# 03_ATSAM3X_LFBGA217.net
KiCad netlist of a schematic drawn in Altium Designer
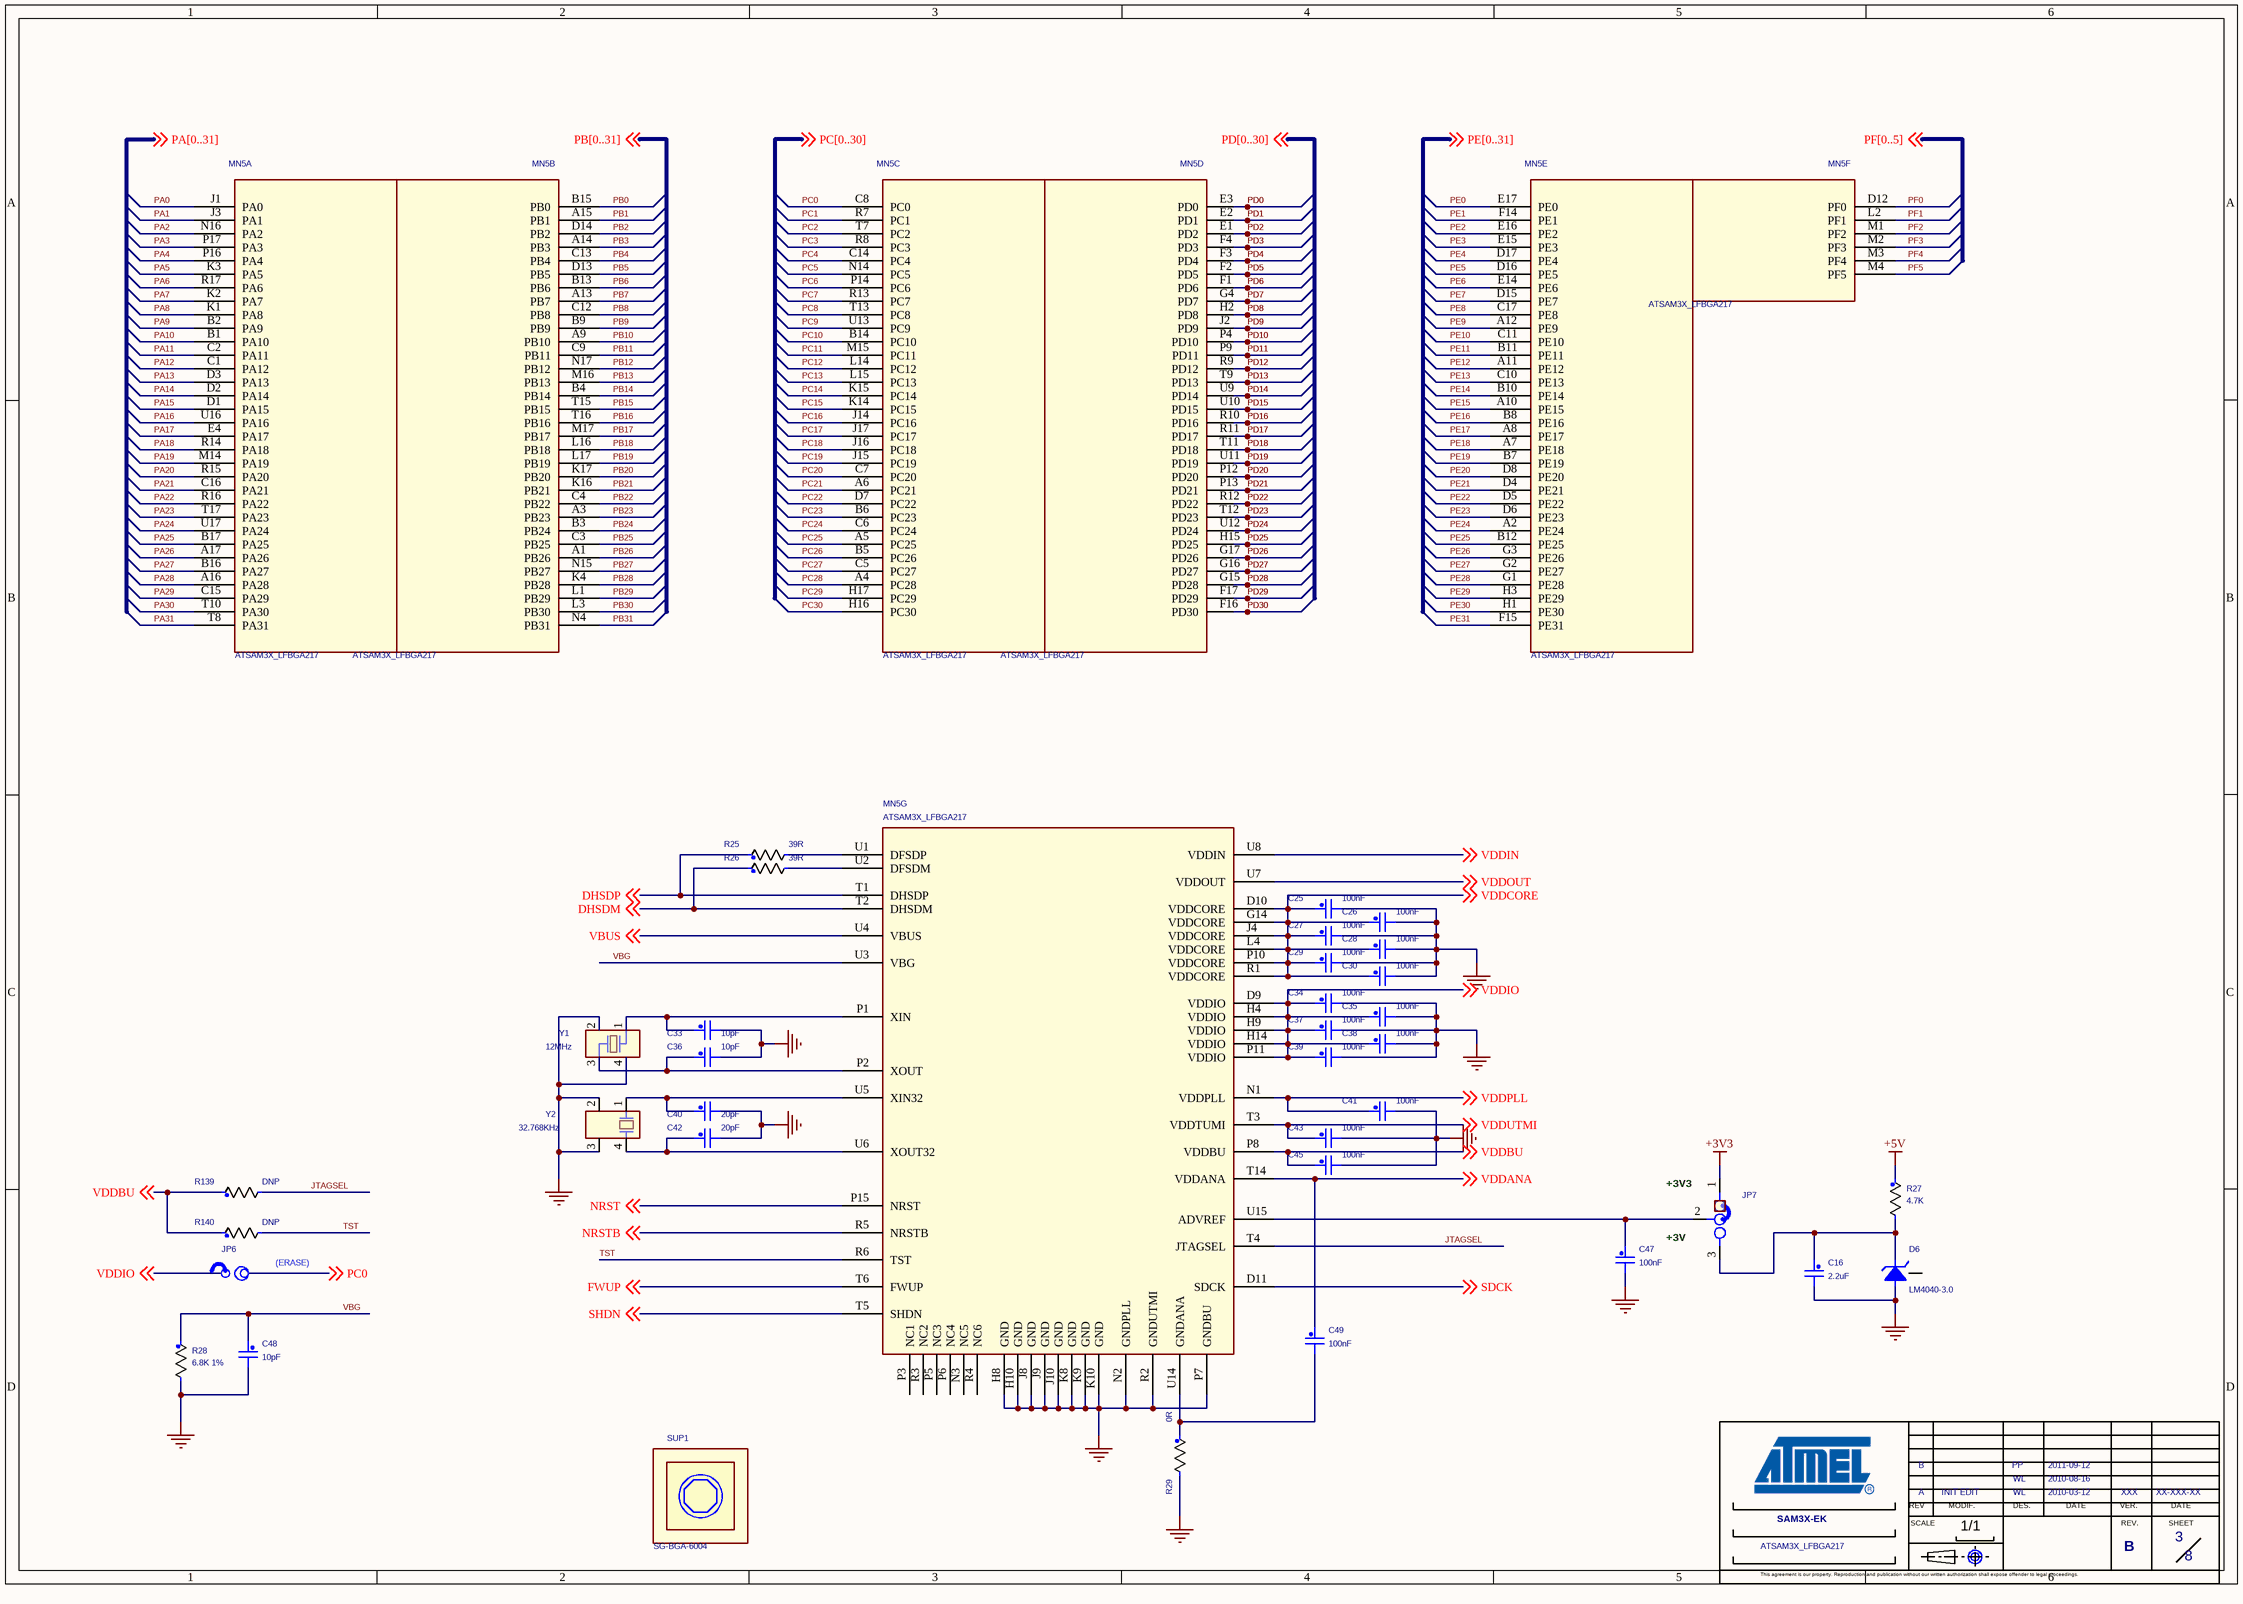
[diagram p0: 03_ATSAM3X_LFBGA217.SchDoc]

(export (version "E")
  (design (tool "Eeschema 10.0.6"))
  (components
    (comp (ref "C16")
      (value "2.2uF")
      (footprint "CAP0805")
      (fields (field (name "VOLTAGE") "50V"))
      (libsource (lib "*") (part "C_Generic"))
    )
    (comp (ref "C25")
      (value "100nF")
      (footprint "CAP0805")
      (fields (field (name "VOLTAGE") "16V"))
      (libsource (lib "*") (part "C_Generic"))
    )
    (comp (ref "C26")
      (value "100nF")
      (footprint "CAP0805")
      (fields (field (name "VOLTAGE") "16V"))
      (libsource (lib "*") (part "C_Generic"))
    )
    (comp (ref "C27")
      (value "100nF")
      (footprint "CAP0805")
      (fields (field (name "VOLTAGE") "16V"))
      (libsource (lib "*") (part "C_Generic"))
    )
    (comp (ref "C28")
      (value "100nF")
      (footprint "CAP0805")
      (fields (field (name "VOLTAGE") "16V"))
      (libsource (lib "*") (part "C_Generic"))
    )
    (comp (ref "C29")
      (value "100nF")
      (footprint "CAP0805")
      (fields (field (name "VOLTAGE") "16V"))
      (libsource (lib "*") (part "C_Generic"))
    )
    (comp (ref "C30")
      (value "100nF")
      (footprint "CAP0805")
      (fields (field (name "VOLTAGE") "16V"))
      (libsource (lib "*") (part "C_Generic"))
    )
    (comp (ref "C33")
      (value "10pF")
      (footprint "CAP0805")
      (fields (field (name "VOLTAGE") "16V"))
      (libsource (lib "*") (part "C_Generic"))
    )
    (comp (ref "C34")
      (value "100nF")
      (footprint "CAP0805")
      (fields (field (name "VOLTAGE") "16V"))
      (libsource (lib "*") (part "C_Generic"))
    )
    (comp (ref "C35")
      (value "100nF")
      (footprint "CAP0805")
      (fields (field (name "VOLTAGE") "16V"))
      (libsource (lib "*") (part "C_Generic"))
    )
    (comp (ref "C36")
      (value "10pF")
      (footprint "CAP0805")
      (fields (field (name "VOLTAGE") "16V"))
      (libsource (lib "*") (part "C_Generic"))
    )
    (comp (ref "C37")
      (value "100nF")
      (footprint "CAP0805")
      (fields (field (name "VOLTAGE") "16V"))
      (libsource (lib "*") (part "C_Generic"))
    )
    (comp (ref "C38")
      (value "100nF")
      (footprint "CAP0805")
      (fields (field (name "VOLTAGE") "16V"))
      (libsource (lib "*") (part "C_Generic"))
    )
    (comp (ref "C39")
      (value "100nF")
      (footprint "CAP0805")
      (fields (field (name "VOLTAGE") "16V"))
      (libsource (lib "*") (part "C_Generic"))
    )
    (comp (ref "C40")
      (value "20pF")
      (footprint "CAP0805")
      (fields (field (name "VOLTAGE") "16V"))
      (libsource (lib "*") (part "C_Generic"))
    )
    (comp (ref "C41")
      (value "100nF")
      (footprint "CAP0805")
      (fields (field (name "VOLTAGE") "16V"))
      (libsource (lib "*") (part "C_Generic"))
    )
    (comp (ref "C42")
      (value "20pF")
      (footprint "CAP0805")
      (fields (field (name "VOLTAGE") "16V"))
      (libsource (lib "*") (part "C_Generic"))
    )
    (comp (ref "C43")
      (value "100nF")
      (footprint "CAP0805")
      (fields (field (name "VOLTAGE") "16V"))
      (libsource (lib "*") (part "C_Generic"))
    )
    (comp (ref "C45")
      (value "100nF")
      (footprint "CAP0805")
      (fields (field (name "VOLTAGE") "16V"))
      (libsource (lib "*") (part "C_Generic"))
    )
    (comp (ref "C47")
      (value "100nF")
      (footprint "CAP0805")
      (fields (field (name "VOLTAGE") "16V"))
      (libsource (lib "*") (part "C_Generic"))
    )
    (comp (ref "C48")
      (value "10pF")
      (footprint "CAP0805")
      (fields (field (name "VOLTAGE") "16V"))
      (libsource (lib "*") (part "C_Generic"))
    )
    (comp (ref "C49")
      (value "100nF")
      (footprint "CAP0805")
      (fields (field (name "VOLTAGE") "16V"))
      (libsource (lib "*") (part "C_Generic"))
    )
    (comp (ref "D6") (value "LM4040-3.0") (footprint "SOT-23") (libsource (lib "*") (part "LM4040")))
    (comp (ref "JP6") (value "JP") (footprint "BAR2PTS02") (libsource (lib "*") (part "JUMP_0")))
    (comp (ref "JP7")
      (value "header3-100")
      (footprint "BAR3PTS02")
      (libsource (lib "*") (part "TSW 3PTS-DROIT_0"))
    )
    (comp (ref "MN5")
      (value "ATSAM3X_LFBGA217")
      (footprint "LFBGA217")
      (libsource (lib "*") (part "ATSAM3X_LFBGA217"))
    )
    (comp (ref "R25") (value "39R") (footprint "R0603") (libsource (lib "*") (part "R_Generic")))
    (comp (ref "R26") (value "39R") (footprint "R0603") (libsource (lib "*") (part "R_Generic")))
    (comp (ref "R27") (value "4.7K") (footprint "R0603") (libsource (lib "*") (part "R_Generic")))
    (comp (ref "R28") (value "6.8K 1%") (footprint "R0603") (libsource (lib "*") (part "R_Generic")))
    (comp (ref "R29") (value "0R") (footprint "r0603") (libsource (lib "*") (part "R_Generic")))
    (comp (ref "R139") (value "DNP") (footprint "r0603") (libsource (lib "*") (part "R_Generic")))
    (comp (ref "R140") (value "DNP") (footprint "r0603") (libsource (lib "*") (part "R_Generic")))
    (comp (ref "SH12")
      (value "Jumper Pitch 2.54")
      (footprint "JUMPER-2.54")
      (description "Jumper,2 Points Jumper Pitch 2.54")
      (fields (field (name "PART NUMBER") "440-00002-1") (field (name "MANUFACTURER") "WIESON"))
      (libsource (lib "*") (part "JUMPER-2.54"))
    )
    (comp (ref "SH13")
      (value "Jumper Pitch 2.54")
      (footprint "JUMPER-2.54")
      (description "Jumper,2 Points Jumper Pitch 2.54")
      (fields
        (field (name "MANUFACTURER PART NUMBER") "G4160-1A60BF1U")
        (field (name "MANUFACTURER") "WIESON")
      )
      (libsource (lib "*") (part "JUMPER-2.54"))
    )
    (comp (ref "SUP1")
      (value "Support_SG-BGA-6004-MF")
      (fields (field (name "VAL") "SG-BGA-6004"))
      (libsource (lib "*") (part "Support_SG-BGA-6004-MF"))
    )
    (comp (ref "Y1") (value "12MHz") (footprint "Y6035") (libsource (lib "*") (part "12MHz")))
    (comp (ref "Y2") (value "32.768KHz") (footprint "9H-T7") (libsource (lib "*") (part "32.768KHz")))
  )
  (nets
    (net (code "1") (name "+3V3") (class "Default")
      (node (ref "JP7") (pin "1") (pinfunction "1_1") (pintype "passive"))
    )
    (net (code "2") (name "+5V") (class "Default")
      (node (ref "R27") (pin "1") (pinfunction "1_1") (pintype "passive"))
    )
    (net (code "3") (name "/JTAGSEL") (class "Default")
      (node (ref "MN5") (pin "T4") (pinfunction "JTAGSEL_T4") (pintype "passive"))
      (node (ref "R139") (pin "2") (pinfunction "2_2") (pintype "passive"))
    )
    (net (code "4") (name "/TST") (class "Default")
      (node (ref "MN5") (pin "R6") (pinfunction "TST_R6") (pintype "passive"))
      (node (ref "R140") (pin "2") (pinfunction "2_2") (pintype "passive"))
    )
    (net (code "5") (name "/VBG") (class "Default")
      (node (ref "C48") (pin "1") (pinfunction "1_1") (pintype "passive"))
      (node (ref "MN5") (pin "U3") (pinfunction "VBG_U3") (pintype "passive"))
      (node (ref "R28") (pin "1") (pinfunction "1_1") (pintype "passive"))
    )
    (net (code "6") (name "DHSDM") (class "Default")
      (node (ref "MN5") (pin "T2") (pinfunction "DHSDM_T2") (pintype "passive"))
      (node (ref "R26") (pin "1") (pinfunction "1_1") (pintype "passive"))
    )
    (net (code "7") (name "DHSDP") (class "Default")
      (node (ref "MN5") (pin "T1") (pinfunction "DHSDP_T1") (pintype "passive"))
      (node (ref "R25") (pin "1") (pinfunction "1_1") (pintype "passive"))
    )
    (net (code "8") (name "FWUP") (class "Default")
      (node (ref "MN5") (pin "T6") (pinfunction "FWUP_T6") (pintype "passive"))
    )
    (net (code "9") (name "GND_POWER") (class "Default")
      (node (ref "C16") (pin "2") (pinfunction "2_2") (pintype "passive"))
      (node (ref "C25") (pin "2") (pinfunction "2_2") (pintype "passive"))
      (node (ref "C26") (pin "2") (pinfunction "2_2") (pintype "passive"))
      (node (ref "C27") (pin "2") (pinfunction "2_2") (pintype "passive"))
      (node (ref "C28") (pin "2") (pinfunction "2_2") (pintype "passive"))
      (node (ref "C29") (pin "2") (pinfunction "2_2") (pintype "passive"))
      (node (ref "C30") (pin "2") (pinfunction "2_2") (pintype "passive"))
      (node (ref "C33") (pin "2") (pinfunction "2_2") (pintype "passive"))
      (node (ref "C34") (pin "2") (pinfunction "2_2") (pintype "passive"))
      (node (ref "C35") (pin "2") (pinfunction "2_2") (pintype "passive"))
      (node (ref "C36") (pin "2") (pinfunction "2_2") (pintype "passive"))
      (node (ref "C37") (pin "2") (pinfunction "2_2") (pintype "passive"))
      (node (ref "C38") (pin "2") (pinfunction "2_2") (pintype "passive"))
      (node (ref "C39") (pin "2") (pinfunction "2_2") (pintype "passive"))
      (node (ref "C40") (pin "2") (pinfunction "2_2") (pintype "passive"))
      (node (ref "C41") (pin "2") (pinfunction "2_2") (pintype "passive"))
      (node (ref "C42") (pin "2") (pinfunction "2_2") (pintype "passive"))
      (node (ref "C43") (pin "2") (pinfunction "2_2") (pintype "passive"))
      (node (ref "C45") (pin "2") (pinfunction "2_2") (pintype "passive"))
      (node (ref "C47") (pin "2") (pinfunction "2_2") (pintype "passive"))
      (node (ref "C48") (pin "2") (pinfunction "2_2") (pintype "passive"))
      (node (ref "D6") (pin "2") (pinfunction "-_2") (pintype "passive"))
      (node (ref "MN5") (pin "H10") (pinfunction "GND_H10") (pintype "power_in"))
      (node (ref "MN5") (pin "H8") (pinfunction "GND_H8") (pintype "power_in"))
      (node (ref "MN5") (pin "J10") (pinfunction "GND_J10") (pintype "power_in"))
      (node (ref "MN5") (pin "J8") (pinfunction "GND_J8") (pintype "power_in"))
      (node (ref "MN5") (pin "J9") (pinfunction "GND_J9") (pintype "power_in"))
      (node (ref "MN5") (pin "K10") (pinfunction "GND_K10") (pintype "power_in"))
      (node (ref "MN5") (pin "K8") (pinfunction "GND_K8") (pintype "power_in"))
      (node (ref "MN5") (pin "K9") (pinfunction "GND_K9") (pintype "power_in"))
      (node (ref "MN5") (pin "N2") (pinfunction "GNDPLL_N2") (pintype "passive"))
      (node (ref "MN5") (pin "P7") (pinfunction "GNDBU_P7") (pintype "power_in"))
      (node (ref "MN5") (pin "R2") (pinfunction "GNDUTMI_R2") (pintype "passive"))
      (node (ref "R28") (pin "2") (pinfunction "2_2") (pintype "passive"))
      (node (ref "R29") (pin "2") (pinfunction "2_2") (pintype "passive"))
      (node (ref "Y1") (pin "2") (pinfunction "2_2") (pintype "passive"))
      (node (ref "Y1") (pin "4") (pinfunction "4_4") (pintype "passive"))
      (node (ref "Y2") (pin "2") (pinfunction "2_2") (pintype "passive"))
      (node (ref "Y2") (pin "3") (pinfunction "3_3") (pintype "passive"))
    )
    (net (code "10") (name "NRST") (class "Default")
      (node (ref "MN5") (pin "P15") (pinfunction "NRST_P15") (pintype "passive"))
    )
    (net (code "11") (name "NRSTB") (class "Default")
      (node (ref "MN5") (pin "R5") (pinfunction "NRSTB_R5") (pintype "passive"))
    )
    (net (code "12") (name "Net-(D6-+)") (class "Default")
      (node (ref "C16") (pin "1") (pinfunction "1_1") (pintype "passive"))
      (node (ref "D6") (pin "1") (pinfunction "+_1") (pintype "passive"))
      (node (ref "JP7") (pin "3") (pinfunction "3_3") (pintype "passive"))
      (node (ref "R27") (pin "2") (pinfunction "2_2") (pintype "passive"))
    )
    (net (code "13") (name "Net-(MN5G-ADVREF)") (class "Default")
      (node (ref "C47") (pin "1") (pinfunction "1_1") (pintype "passive"))
      (node (ref "JP7") (pin "2") (pinfunction "2_2") (pintype "passive"))
      (node (ref "MN5") (pin "U15") (pinfunction "ADVREF_U15") (pintype "passive"))
    )
    (net (code "14") (name "Net-(MN5G-DFSDM)") (class "Default")
      (node (ref "MN5") (pin "U2") (pinfunction "DFSDM_U2") (pintype "passive"))
      (node (ref "R26") (pin "2") (pinfunction "2_2") (pintype "passive"))
    )
    (net (code "15") (name "Net-(MN5G-DFSDP)") (class "Default")
      (node (ref "MN5") (pin "U1") (pinfunction "DFSDP_U1") (pintype "passive"))
      (node (ref "R25") (pin "2") (pinfunction "2_2") (pintype "passive"))
    )
    (net (code "16") (name "Net-(MN5G-GNDANA)") (class "Default")
      (node (ref "C49") (pin "2") (pinfunction "2_2") (pintype "passive"))
      (node (ref "MN5") (pin "U14") (pinfunction "GNDANA_U14") (pintype "passive"))
      (node (ref "R29") (pin "1") (pinfunction "1_1") (pintype "passive"))
    )
    (net (code "17") (name "Net-(MN5G-XIN)") (class "Default")
      (node (ref "C33") (pin "1") (pinfunction "1_1") (pintype "passive"))
      (node (ref "MN5") (pin "P1") (pinfunction "XIN_P1") (pintype "passive"))
      (node (ref "Y1") (pin "1") (pinfunction "1_1") (pintype "passive"))
    )
    (net (code "18") (name "Net-(MN5G-XIN32)") (class "Default")
      (node (ref "C40") (pin "1") (pinfunction "1_1") (pintype "passive"))
      (node (ref "MN5") (pin "U5") (pinfunction "XIN32_U5") (pintype "passive"))
      (node (ref "Y2") (pin "1") (pinfunction "1_1") (pintype "passive"))
    )
    (net (code "19") (name "Net-(MN5G-XOUT)") (class "Default")
      (node (ref "C36") (pin "1") (pinfunction "1_1") (pintype "passive"))
      (node (ref "MN5") (pin "P2") (pinfunction "XOUT_P2") (pintype "passive"))
      (node (ref "Y1") (pin "3") (pinfunction "3_3") (pintype "passive"))
    )
    (net (code "20") (name "Net-(MN5G-XOUT32)") (class "Default")
      (node (ref "C42") (pin "1") (pinfunction "1_1") (pintype "passive"))
      (node (ref "MN5") (pin "U6") (pinfunction "XOUT32_U6") (pintype "passive"))
      (node (ref "Y2") (pin "4") (pinfunction "4_4") (pintype "passive"))
    )
    (net (code "21") (name "PA0") (class "Default")
      (node (ref "MN5") (pin "J1") (pinfunction "PA0_J1") (pintype "passive"))
    )
    (net (code "22") (name "PA1") (class "Default")
      (node (ref "MN5") (pin "J3") (pinfunction "PA1_J3") (pintype "passive"))
    )
    (net (code "23") (name "PA2") (class "Default")
      (node (ref "MN5") (pin "N16") (pinfunction "PA2_N16") (pintype "passive"))
    )
    (net (code "24") (name "PA3") (class "Default")
      (node (ref "MN5") (pin "P17") (pinfunction "PA3_P17") (pintype "passive"))
    )
    (net (code "25") (name "PA4") (class "Default")
      (node (ref "MN5") (pin "P16") (pinfunction "PA4_P16") (pintype "passive"))
    )
    (net (code "26") (name "PA5") (class "Default")
      (node (ref "MN5") (pin "K3") (pinfunction "PA5_K3") (pintype "passive"))
    )
    (net (code "27") (name "PA6") (class "Default")
      (node (ref "MN5") (pin "R17") (pinfunction "PA6_R17") (pintype "passive"))
    )
    (net (code "28") (name "PA7") (class "Default")
      (node (ref "MN5") (pin "K2") (pinfunction "PA7_K2") (pintype "passive"))
    )
    (net (code "29") (name "PA8") (class "Default")
      (node (ref "MN5") (pin "K1") (pinfunction "PA8_K1") (pintype "passive"))
    )
    (net (code "30") (name "PA9") (class "Default")
      (node (ref "MN5") (pin "B2") (pinfunction "PA9_B2") (pintype "passive"))
    )
    (net (code "31") (name "PA10") (class "Default")
      (node (ref "MN5") (pin "B1") (pinfunction "PA10_B1") (pintype "passive"))
    )
    (net (code "32") (name "PA11") (class "Default")
      (node (ref "MN5") (pin "C2") (pinfunction "PA11_C2") (pintype "passive"))
    )
    (net (code "33") (name "PA12") (class "Default")
      (node (ref "MN5") (pin "C1") (pinfunction "PA12_C1") (pintype "passive"))
    )
    (net (code "34") (name "PA13") (class "Default")
      (node (ref "MN5") (pin "D3") (pinfunction "PA13_D3") (pintype "passive"))
    )
    (net (code "35") (name "PA14") (class "Default")
      (node (ref "MN5") (pin "D2") (pinfunction "PA14_D2") (pintype "passive"))
    )
    (net (code "36") (name "PA15") (class "Default")
      (node (ref "MN5") (pin "D1") (pinfunction "PA15_D1") (pintype "passive"))
    )
    (net (code "37") (name "PA16") (class "Default")
      (node (ref "MN5") (pin "U16") (pinfunction "PA16_U16") (pintype "passive"))
    )
    (net (code "38") (name "PA17") (class "Default")
      (node (ref "MN5") (pin "E4") (pinfunction "PA17_E4") (pintype "passive"))
    )
    (net (code "39") (name "PA18") (class "Default")
      (node (ref "MN5") (pin "R14") (pinfunction "PA18_R14") (pintype "passive"))
    )
    (net (code "40") (name "PA19") (class "Default")
      (node (ref "MN5") (pin "M14") (pinfunction "PA19_M14") (pintype "passive"))
    )
    (net (code "41") (name "PA20") (class "Default")
      (node (ref "MN5") (pin "R15") (pinfunction "PA20_R15") (pintype "passive"))
    )
    (net (code "42") (name "PA21") (class "Default")
      (node (ref "MN5") (pin "C16") (pinfunction "PA21_C16") (pintype "passive"))
    )
    (net (code "43") (name "PA22") (class "Default")
      (node (ref "MN5") (pin "R16") (pinfunction "PA22_R16") (pintype "passive"))
    )
    (net (code "44") (name "PA23") (class "Default")
      (node (ref "MN5") (pin "T17") (pinfunction "PA23_T17") (pintype "passive"))
    )
    (net (code "45") (name "PA24") (class "Default")
      (node (ref "MN5") (pin "U17") (pinfunction "PA24_U17") (pintype "passive"))
    )
    (net (code "46") (name "PA25") (class "Default")
      (node (ref "MN5") (pin "B17") (pinfunction "PA25_B17") (pintype "passive"))
    )
    (net (code "47") (name "PA26") (class "Default")
      (node (ref "MN5") (pin "A17") (pinfunction "PA26_A17") (pintype "passive"))
    )
    (net (code "48") (name "PA27") (class "Default")
      (node (ref "MN5") (pin "B16") (pinfunction "PA27_B16") (pintype "passive"))
    )
    (net (code "49") (name "PA28") (class "Default")
      (node (ref "MN5") (pin "A16") (pinfunction "PA28_A16") (pintype "passive"))
    )
    (net (code "50") (name "PA29") (class "Default")
      (node (ref "MN5") (pin "C15") (pinfunction "PA29_C15") (pintype "passive"))
    )
    (net (code "51") (name "PA30") (class "Default")
      (node (ref "MN5") (pin "T10") (pinfunction "PA30_T10") (pintype "passive"))
    )
    (net (code "52") (name "PA31") (class "Default")
      (node (ref "MN5") (pin "T8") (pinfunction "PA31_T8") (pintype "passive"))
    )
    (net (code "54") (name "PB0") (class "Default")
      (node (ref "MN5") (pin "B15") (pinfunction "PB0_B15") (pintype "passive"))
    )
    (net (code "55") (name "PB1") (class "Default")
      (node (ref "MN5") (pin "A15") (pinfunction "PB1_A15") (pintype "passive"))
    )
    (net (code "56") (name "PB2") (class "Default")
      (node (ref "MN5") (pin "D14") (pinfunction "PB2_D14") (pintype "passive"))
    )
    (net (code "57") (name "PB3") (class "Default")
      (node (ref "MN5") (pin "A14") (pinfunction "PB3_A14") (pintype "passive"))
    )
    (net (code "58") (name "PB4") (class "Default")
      (node (ref "MN5") (pin "C13") (pinfunction "PB4_C13") (pintype "passive"))
    )
    (net (code "59") (name "PB5") (class "Default")
      (node (ref "MN5") (pin "D13") (pinfunction "PB5_D13") (pintype "passive"))
    )
    (net (code "60") (name "PB6") (class "Default")
      (node (ref "MN5") (pin "B13") (pinfunction "PB6_B13") (pintype "passive"))
    )
    (net (code "61") (name "PB7") (class "Default")
      (node (ref "MN5") (pin "A13") (pinfunction "PB7_A13") (pintype "passive"))
    )
    (net (code "62") (name "PB8") (class "Default")
      (node (ref "MN5") (pin "C12") (pinfunction "PB8_C12") (pintype "passive"))
    )
    (net (code "63") (name "PB9") (class "Default")
      (node (ref "MN5") (pin "B9") (pinfunction "PB9_B9") (pintype "passive"))
    )
    (net (code "64") (name "PB10") (class "Default")
      (node (ref "MN5") (pin "A9") (pinfunction "PB10_A9") (pintype "passive"))
    )
    (net (code "65") (name "PB11") (class "Default")
      (node (ref "MN5") (pin "C9") (pinfunction "PB11_C9") (pintype "passive"))
    )
    (net (code "66") (name "PB12") (class "Default")
      (node (ref "MN5") (pin "N17") (pinfunction "PB12_N17") (pintype "passive"))
    )
    (net (code "67") (name "PB13") (class "Default")
      (node (ref "MN5") (pin "M16") (pinfunction "PB13_M16") (pintype "passive"))
    )
    (net (code "68") (name "PB14") (class "Default")
      (node (ref "MN5") (pin "B4") (pinfunction "PB14_B4") (pintype "passive"))
    )
    (net (code "69") (name "PB15") (class "Default")
      (node (ref "MN5") (pin "T15") (pinfunction "PB15_T15") (pintype "passive"))
    )
    (net (code "70") (name "PB16") (class "Default")
      (node (ref "MN5") (pin "T16") (pinfunction "PB16_T16") (pintype "passive"))
    )
    (net (code "71") (name "PB17") (class "Default")
      (node (ref "MN5") (pin "M17") (pinfunction "PB17_M17") (pintype "passive"))
    )
    (net (code "72") (name "PB18") (class "Default")
      (node (ref "MN5") (pin "L16") (pinfunction "PB18_L16") (pintype "passive"))
    )
    (net (code "73") (name "PB19") (class "Default")
      (node (ref "MN5") (pin "L17") (pinfunction "PB19_L17") (pintype "passive"))
    )
    (net (code "74") (name "PB20") (class "Default")
      (node (ref "MN5") (pin "K17") (pinfunction "PB20_K17") (pintype "passive"))
    )
    (net (code "75") (name "PB21") (class "Default")
      (node (ref "MN5") (pin "K16") (pinfunction "PB21_K16") (pintype "passive"))
    )
    (net (code "76") (name "PB22") (class "Default")
      (node (ref "MN5") (pin "C4") (pinfunction "PB22_C4") (pintype "passive"))
    )
    (net (code "77") (name "PB23") (class "Default")
      (node (ref "MN5") (pin "A3") (pinfunction "PB23_A3") (pintype "passive"))
    )
    (net (code "78") (name "PB24") (class "Default")
      (node (ref "MN5") (pin "B3") (pinfunction "PB24_B3") (pintype "passive"))
    )
    (net (code "79") (name "PB25") (class "Default")
      (node (ref "MN5") (pin "C3") (pinfunction "PB25_C3") (pintype "passive"))
    )
    (net (code "80") (name "PB26") (class "Default")
      (node (ref "MN5") (pin "A1") (pinfunction "PB26_A1") (pintype "passive"))
    )
    (net (code "81") (name "PB27") (class "Default")
      (node (ref "MN5") (pin "N15") (pinfunction "PB27_N15") (pintype "passive"))
    )
    (net (code "82") (name "PB28") (class "Default")
      (node (ref "MN5") (pin "K4") (pinfunction "PB28_K4") (pintype "passive"))
    )
    (net (code "83") (name "PB29") (class "Default")
      (node (ref "MN5") (pin "L1") (pinfunction "PB29_L1") (pintype "passive"))
    )
    (net (code "84") (name "PB30") (class "Default")
      (node (ref "MN5") (pin "L3") (pinfunction "PB30_L3") (pintype "passive"))
    )
    (net (code "85") (name "PB31") (class "Default")
      (node (ref "MN5") (pin "N4") (pinfunction "PB31_N4") (pintype "passive"))
    )
    (net (code "87") (name "PC0") (class "Default")
      (node (ref "JP6") (pin "1") (pinfunction "1_1") (pintype "passive"))
      (node (ref "MN5") (pin "C8") (pinfunction "PC0_C8") (pintype "passive"))
    )
    (net (code "88") (name "PC1") (class "Default")
      (node (ref "MN5") (pin "R7") (pinfunction "PC1_R7") (pintype "passive"))
    )
    (net (code "89") (name "PC2") (class "Default")
      (node (ref "MN5") (pin "T7") (pinfunction "PC2_T7") (pintype "passive"))
    )
    (net (code "90") (name "PC3") (class "Default")
      (node (ref "MN5") (pin "R8") (pinfunction "PC3_R8") (pintype "passive"))
    )
    (net (code "91") (name "PC4") (class "Default")
      (node (ref "MN5") (pin "C14") (pinfunction "PC4_C14") (pintype "passive"))
    )
    (net (code "92") (name "PC5") (class "Default")
      (node (ref "MN5") (pin "N14") (pinfunction "PC5_N14") (pintype "passive"))
    )
    (net (code "93") (name "PC6") (class "Default")
      (node (ref "MN5") (pin "P14") (pinfunction "PC6_P14") (pintype "passive"))
    )
    (net (code "94") (name "PC7") (class "Default")
      (node (ref "MN5") (pin "R13") (pinfunction "PC7_R13") (pintype "passive"))
    )
    (net (code "95") (name "PC8") (class "Default")
      (node (ref "MN5") (pin "T13") (pinfunction "PC8_T13") (pintype "passive"))
    )
    (net (code "96") (name "PC9") (class "Default")
      (node (ref "MN5") (pin "U13") (pinfunction "PC9_U13") (pintype "passive"))
    )
    (net (code "97") (name "PC10") (class "Default")
      (node (ref "MN5") (pin "B14") (pinfunction "PC10_B14") (pintype "passive"))
    )
    (net (code "98") (name "PC11") (class "Default")
      (node (ref "MN5") (pin "M15") (pinfunction "PC11_M15") (pintype "passive"))
    )
    (net (code "99") (name "PC12") (class "Default")
      (node (ref "MN5") (pin "L14") (pinfunction "PC12_L14") (pintype "passive"))
    )
    (net (code "100") (name "PC13") (class "Default")
      (node (ref "MN5") (pin "L15") (pinfunction "PC13_L15") (pintype "passive"))
    )
    (net (code "101") (name "PC14") (class "Default")
      (node (ref "MN5") (pin "K15") (pinfunction "PC14_K15") (pintype "passive"))
    )
    (net (code "102") (name "PC15") (class "Default")
      (node (ref "MN5") (pin "K14") (pinfunction "PC15_K14") (pintype "passive"))
    )
    (net (code "103") (name "PC16") (class "Default")
      (node (ref "MN5") (pin "J14") (pinfunction "PC16_J14") (pintype "passive"))
    )
    (net (code "104") (name "PC17") (class "Default")
      (node (ref "MN5") (pin "J17") (pinfunction "PC17_J17") (pintype "passive"))
    )
    (net (code "105") (name "PC18") (class "Default")
      (node (ref "MN5") (pin "J16") (pinfunction "PC18_J16") (pintype "passive"))
    )
    (net (code "106") (name "PC19") (class "Default")
      (node (ref "MN5") (pin "J15") (pinfunction "PC19_J15") (pintype "passive"))
    )
    (net (code "107") (name "PC20") (class "Default")
      (node (ref "MN5") (pin "C7") (pinfunction "PC20_C7") (pintype "passive"))
    )
    (net (code "108") (name "PC21") (class "Default")
      (node (ref "MN5") (pin "A6") (pinfunction "PC21_A6") (pintype "passive"))
    )
    (net (code "109") (name "PC22") (class "Default")
      (node (ref "MN5") (pin "D7") (pinfunction "PC22_D7") (pintype "passive"))
    )
    (net (code "110") (name "PC23") (class "Default")
      (node (ref "MN5") (pin "B6") (pinfunction "PC23_B6") (pintype "passive"))
    )
    (net (code "111") (name "PC24") (class "Default")
      (node (ref "MN5") (pin "C6") (pinfunction "PC24_C6") (pintype "passive"))
    )
    (net (code "112") (name "PC25") (class "Default")
      (node (ref "MN5") (pin "A5") (pinfunction "PC25_A5") (pintype "passive"))
    )
    (net (code "113") (name "PC26") (class "Default")
      (node (ref "MN5") (pin "B5") (pinfunction "PC26_B5") (pintype "passive"))
    )
    (net (code "114") (name "PC27") (class "Default")
      (node (ref "MN5") (pin "C5") (pinfunction "PC27_C5") (pintype "passive"))
    )
    (net (code "115") (name "PC28") (class "Default")
      (node (ref "MN5") (pin "A4") (pinfunction "PC28_A4") (pintype "passive"))
    )
    (net (code "116") (name "PC29") (class "Default")
      (node (ref "MN5") (pin "H17") (pinfunction "PC29_H17") (pintype "passive"))
    )
    (net (code "117") (name "PC30") (class "Default")
      (node (ref "MN5") (pin "H16") (pinfunction "PC30_H16") (pintype "passive"))
    )
    (net (code "119") (name "PD0") (class "Default")
      (node (ref "MN5") (pin "E3") (pinfunction "PD0_E3") (pintype "passive"))
    )
    (net (code "120") (name "PD1") (class "Default")
      (node (ref "MN5") (pin "E2") (pinfunction "PD1_E2") (pintype "passive"))
    )
    (net (code "121") (name "PD2") (class "Default")
      (node (ref "MN5") (pin "E1") (pinfunction "PD2_E1") (pintype "passive"))
    )
    (net (code "122") (name "PD3") (class "Default")
      (node (ref "MN5") (pin "F4") (pinfunction "PD3_F4") (pintype "passive"))
    )
    (net (code "123") (name "PD4") (class "Default")
      (node (ref "MN5") (pin "F3") (pinfunction "PD4_F3") (pintype "passive"))
    )
    (net (code "124") (name "PD5") (class "Default")
      (node (ref "MN5") (pin "F2") (pinfunction "PD5_F2") (pintype "passive"))
    )
    (net (code "125") (name "PD6") (class "Default")
      (node (ref "MN5") (pin "F1") (pinfunction "PD6_F1") (pintype "passive"))
    )
    (net (code "126") (name "PD7") (class "Default")
      (node (ref "MN5") (pin "G4") (pinfunction "PD7_G4") (pintype "passive"))
    )
    (net (code "127") (name "PD8") (class "Default")
      (node (ref "MN5") (pin "H2") (pinfunction "PD8_H2") (pintype "passive"))
    )
    (net (code "128") (name "PD9") (class "Default")
      (node (ref "MN5") (pin "J2") (pinfunction "PD9_J2") (pintype "passive"))
    )
    (net (code "129") (name "PD10") (class "Default")
      (node (ref "MN5") (pin "P4") (pinfunction "PD10_P4") (pintype "passive"))
    )
    (net (code "130") (name "PD11") (class "Default")
      (node (ref "MN5") (pin "P9") (pinfunction "PD11_P9") (pintype "passive"))
    )
    (net (code "131") (name "PD12") (class "Default")
      (node (ref "MN5") (pin "R9") (pinfunction "PD12_R9") (pintype "passive"))
    )
    (net (code "132") (name "PD13") (class "Default")
      (node (ref "MN5") (pin "T9") (pinfunction "PD13_T9") (pintype "passive"))
    )
    (net (code "133") (name "PD14") (class "Default")
      (node (ref "MN5") (pin "U9") (pinfunction "PD14_U9") (pintype "passive"))
    )
    (net (code "134") (name "PD15") (class "Default")
      (node (ref "MN5") (pin "U10") (pinfunction "PD15_U10") (pintype "passive"))
    )
    (net (code "135") (name "PD16") (class "Default")
      (node (ref "MN5") (pin "R10") (pinfunction "PD16_R10") (pintype "passive"))
    )
    (net (code "136") (name "PD17") (class "Default")
      (node (ref "MN5") (pin "R11") (pinfunction "PD17_R11") (pintype "passive"))
    )
    (net (code "137") (name "PD18") (class "Default")
      (node (ref "MN5") (pin "T11") (pinfunction "PD18_T11") (pintype "passive"))
    )
    (net (code "138") (name "PD19") (class "Default")
      (node (ref "MN5") (pin "U11") (pinfunction "PD19_U11") (pintype "passive"))
    )
    (net (code "139") (name "PD20") (class "Default")
      (node (ref "MN5") (pin "P12") (pinfunction "PD20_P12") (pintype "passive"))
    )
    (net (code "140") (name "PD21") (class "Default")
      (node (ref "MN5") (pin "P13") (pinfunction "PD21_P13") (pintype "passive"))
    )
    (net (code "141") (name "PD22") (class "Default")
      (node (ref "MN5") (pin "R12") (pinfunction "PD22_R12") (pintype "passive"))
    )
    (net (code "142") (name "PD23") (class "Default")
      (node (ref "MN5") (pin "T12") (pinfunction "PD23_T12") (pintype "passive"))
    )
    (net (code "143") (name "PD24") (class "Default")
      (node (ref "MN5") (pin "U12") (pinfunction "PD24_U12") (pintype "passive"))
    )
    (net (code "144") (name "PD25") (class "Default")
      (node (ref "MN5") (pin "H15") (pinfunction "PD25_H15") (pintype "passive"))
    )
    (net (code "145") (name "PD26") (class "Default")
      (node (ref "MN5") (pin "G17") (pinfunction "PD26_G17") (pintype "passive"))
    )
    (net (code "146") (name "PD27") (class "Default")
      (node (ref "MN5") (pin "G16") (pinfunction "PD27_G16") (pintype "passive"))
    )
    (net (code "147") (name "PD28") (class "Default")
      (node (ref "MN5") (pin "G15") (pinfunction "PD28_G15") (pintype "passive"))
    )
    (net (code "148") (name "PD29") (class "Default")
      (node (ref "MN5") (pin "F17") (pinfunction "PD29_F17") (pintype "passive"))
    )
    (net (code "149") (name "PD30") (class "Default")
      (node (ref "MN5") (pin "F16") (pinfunction "PD30_F16") (pintype "passive"))
    )
    (net (code "151") (name "PE0") (class "Default")
      (node (ref "MN5") (pin "E17") (pinfunction "PE0_E17") (pintype "passive"))
    )
    (net (code "152") (name "PE1") (class "Default")
      (node (ref "MN5") (pin "F14") (pinfunction "PE1_F14") (pintype "passive"))
    )
    (net (code "153") (name "PE2") (class "Default")
      (node (ref "MN5") (pin "E16") (pinfunction "PE2_E16") (pintype "passive"))
    )
    (net (code "154") (name "PE3") (class "Default")
      (node (ref "MN5") (pin "E15") (pinfunction "PE3_E15") (pintype "passive"))
    )
    (net (code "155") (name "PE4") (class "Default")
      (node (ref "MN5") (pin "D17") (pinfunction "PE4_D17") (pintype "passive"))
    )
    (net (code "156") (name "PE5") (class "Default")
      (node (ref "MN5") (pin "D16") (pinfunction "PE5_D16") (pintype "passive"))
    )
    (net (code "157") (name "PE6") (class "Default")
      (node (ref "MN5") (pin "E14") (pinfunction "PE6_E14") (pintype "passive"))
    )
    (net (code "158") (name "PE7") (class "Default")
      (node (ref "MN5") (pin "D15") (pinfunction "PE7_D15") (pintype "passive"))
    )
    (net (code "159") (name "PE8") (class "Default")
      (node (ref "MN5") (pin "C17") (pinfunction "PE8_C17") (pintype "passive"))
    )
    (net (code "160") (name "PE9") (class "Default")
      (node (ref "MN5") (pin "A12") (pinfunction "PE9_A12") (pintype "passive"))
    )
    (net (code "161") (name "PE10") (class "Default")
      (node (ref "MN5") (pin "C11") (pinfunction "PE10_C11") (pintype "passive"))
    )
    (net (code "162") (name "PE11") (class "Default")
      (node (ref "MN5") (pin "B11") (pinfunction "PE11_B11") (pintype "passive"))
    )
    (net (code "163") (name "PE12") (class "Default")
      (node (ref "MN5") (pin "A11") (pinfunction "PE12_A11") (pintype "passive"))
    )
    (net (code "164") (name "PE13") (class "Default")
      (node (ref "MN5") (pin "C10") (pinfunction "PE13_C10") (pintype "passive"))
    )
    (net (code "165") (name "PE14") (class "Default")
      (node (ref "MN5") (pin "B10") (pinfunction "PE14_B10") (pintype "passive"))
    )
    (net (code "166") (name "PE15") (class "Default")
      (node (ref "MN5") (pin "A10") (pinfunction "PE15_A10") (pintype "passive"))
    )
    (net (code "167") (name "PE16") (class "Default")
      (node (ref "MN5") (pin "B8") (pinfunction "PE16_B8") (pintype "passive"))
    )
    (net (code "168") (name "PE17") (class "Default")
      (node (ref "MN5") (pin "A8") (pinfunction "PE17_A8") (pintype "passive"))
    )
    (net (code "169") (name "PE18") (class "Default")
      (node (ref "MN5") (pin "A7") (pinfunction "PE18_A7") (pintype "passive"))
    )
    (net (code "170") (name "PE19") (class "Default")
      (node (ref "MN5") (pin "B7") (pinfunction "PE19_B7") (pintype "passive"))
    )
    (net (code "171") (name "PE20") (class "Default")
      (node (ref "MN5") (pin "D8") (pinfunction "PE20_D8") (pintype "passive"))
    )
    (net (code "172") (name "PE21") (class "Default")
      (node (ref "MN5") (pin "D4") (pinfunction "PE21_D4") (pintype "passive"))
    )
    (net (code "173") (name "PE22") (class "Default")
      (node (ref "MN5") (pin "D5") (pinfunction "PE22_D5") (pintype "passive"))
    )
    (net (code "174") (name "PE23") (class "Default")
      (node (ref "MN5") (pin "D6") (pinfunction "PE23_D6") (pintype "passive"))
    )
    (net (code "175") (name "PE24") (class "Default")
      (node (ref "MN5") (pin "A2") (pinfunction "PE24_A2") (pintype "passive"))
    )
    (net (code "176") (name "PE25") (class "Default")
      (node (ref "MN5") (pin "B12") (pinfunction "PE25_B12") (pintype "passive"))
    )
    (net (code "177") (name "PE26") (class "Default")
      (node (ref "MN5") (pin "G3") (pinfunction "PE26_G3") (pintype "passive"))
    )
    (net (code "178") (name "PE27") (class "Default")
      (node (ref "MN5") (pin "G2") (pinfunction "PE27_G2") (pintype "passive"))
    )
    (net (code "179") (name "PE28") (class "Default")
      (node (ref "MN5") (pin "G1") (pinfunction "PE28_G1") (pintype "passive"))
    )
    (net (code "180") (name "PE29") (class "Default")
      (node (ref "MN5") (pin "H3") (pinfunction "PE29_H3") (pintype "passive"))
    )
    (net (code "181") (name "PE30") (class "Default")
      (node (ref "MN5") (pin "H1") (pinfunction "PE30_H1") (pintype "passive"))
    )
    (net (code "182") (name "PE31") (class "Default")
      (node (ref "MN5") (pin "F15") (pinfunction "PE31_F15") (pintype "passive"))
    )
    (net (code "184") (name "PF0") (class "Default")
      (node (ref "MN5") (pin "D12") (pinfunction "PF0_D12") (pintype "passive"))
    )
    (net (code "185") (name "PF1") (class "Default")
      (node (ref "MN5") (pin "L2") (pinfunction "PF1_L2") (pintype "passive"))
    )
    (net (code "186") (name "PF2") (class "Default")
      (node (ref "MN5") (pin "M1") (pinfunction "PF2_M1") (pintype "passive"))
    )
    (net (code "187") (name "PF3") (class "Default")
      (node (ref "MN5") (pin "M2") (pinfunction "PF3_M2") (pintype "passive"))
    )
    (net (code "188") (name "PF4") (class "Default")
      (node (ref "MN5") (pin "M3") (pinfunction "PF4_M3") (pintype "passive"))
    )
    (net (code "189") (name "PF5") (class "Default")
      (node (ref "MN5") (pin "M4") (pinfunction "PF5_M4") (pintype "passive"))
    )
    (net (code "191") (name "SDCK") (class "Default")
      (node (ref "MN5") (pin "D11") (pinfunction "SDCK_D11") (pintype "passive"))
    )
    (net (code "192") (name "SHDN") (class "Default")
      (node (ref "MN5") (pin "T5") (pinfunction "SHDN_T5") (pintype "passive"))
    )
    (net (code "193") (name "VBUS") (class "Default")
      (node (ref "MN5") (pin "U4") (pinfunction "VBUS_U4") (pintype "passive"))
    )
    (net (code "194") (name "VDDANA") (class "Default")
      (node (ref "C49") (pin "1") (pinfunction "1_1") (pintype "passive"))
      (node (ref "MN5") (pin "T14") (pinfunction "VDDANA_T14") (pintype "passive"))
    )
    (net (code "195") (name "VDDBU") (class "Default")
      (node (ref "C45") (pin "1") (pinfunction "1_1") (pintype "passive"))
      (node (ref "MN5") (pin "P8") (pinfunction "VDDBU_P8") (pintype "power_in"))
      (node (ref "R139") (pin "1") (pinfunction "1_1") (pintype "passive"))
      (node (ref "R140") (pin "1") (pinfunction "1_1") (pintype "passive"))
    )
    (net (code "196") (name "VDDCORE") (class "Default")
      (node (ref "C25") (pin "1") (pinfunction "1_1") (pintype "passive"))
      (node (ref "C26") (pin "1") (pinfunction "1_1") (pintype "passive"))
      (node (ref "C27") (pin "1") (pinfunction "1_1") (pintype "passive"))
      (node (ref "C28") (pin "1") (pinfunction "1_1") (pintype "passive"))
      (node (ref "C29") (pin "1") (pinfunction "1_1") (pintype "passive"))
      (node (ref "C30") (pin "1") (pinfunction "1_1") (pintype "passive"))
      (node (ref "MN5") (pin "D10") (pinfunction "VDDCORE_D10") (pintype "power_in"))
      (node (ref "MN5") (pin "G14") (pinfunction "VDDCORE_G14") (pintype "power_in"))
      (node (ref "MN5") (pin "J4") (pinfunction "VDDCORE_J4") (pintype "power_in"))
      (node (ref "MN5") (pin "L4") (pinfunction "VDDCORE_L4") (pintype "power_in"))
      (node (ref "MN5") (pin "P10") (pinfunction "VDDCORE_P10") (pintype "power_in"))
      (node (ref "MN5") (pin "R1") (pinfunction "VDDCORE_R1") (pintype "power_in"))
    )
    (net (code "197") (name "VDDIN") (class "Default")
      (node (ref "MN5") (pin "U8") (pinfunction "VDDIN_U8") (pintype "passive"))
    )
    (net (code "198") (name "VDDIO") (class "Default")
      (node (ref "C34") (pin "1") (pinfunction "1_1") (pintype "passive"))
      (node (ref "C35") (pin "1") (pinfunction "1_1") (pintype "passive"))
      (node (ref "C37") (pin "1") (pinfunction "1_1") (pintype "passive"))
      (node (ref "C38") (pin "1") (pinfunction "1_1") (pintype "passive"))
      (node (ref "C39") (pin "1") (pinfunction "1_1") (pintype "passive"))
      (node (ref "JP6") (pin "2") (pinfunction "2_2") (pintype "passive"))
      (node (ref "MN5") (pin "D9") (pinfunction "VDDIO_D9") (pintype "power_in"))
      (node (ref "MN5") (pin "H14") (pinfunction "VDDIO_H14") (pintype "power_in"))
      (node (ref "MN5") (pin "H4") (pinfunction "VDDIO_H4") (pintype "power_in"))
      (node (ref "MN5") (pin "H9") (pinfunction "VDDIO_H9") (pintype "power_in"))
      (node (ref "MN5") (pin "P11") (pinfunction "VDDIO_P11") (pintype "power_in"))
    )
    (net (code "199") (name "VDDOUT") (class "Default")
      (node (ref "MN5") (pin "U7") (pinfunction "VDDOUT_U7") (pintype "passive"))
    )
    (net (code "200") (name "VDDPLL") (class "Default")
      (node (ref "C41") (pin "1") (pinfunction "1_1") (pintype "passive"))
      (node (ref "MN5") (pin "N1") (pinfunction "VDDPLL_N1") (pintype "passive"))
    )
    (net (code "201") (name "VDDUTMI") (class "Default")
      (node (ref "C43") (pin "1") (pinfunction "1_1") (pintype "passive"))
      (node (ref "MN5") (pin "T3") (pinfunction "VDDTUMI_T3") (pintype "power_in"))
    )
    (net (code "202") (name "unconnected-(D6-NC-Pad3)") (class "Default")
      (node (ref "D6") (pin "3") (pinfunction "NC_3") (pintype "passive"))
    )
    (net (code "203") (name "unconnected-(MN5G-NC1-PadP3)") (class "Default")
      (node (ref "MN5") (pin "P3") (pinfunction "NC1_P3") (pintype "passive"))
    )
    (net (code "204") (name "unconnected-(MN5G-NC2-PadR3)") (class "Default")
      (node (ref "MN5") (pin "R3") (pinfunction "NC2_R3") (pintype "passive"))
    )
    (net (code "205") (name "unconnected-(MN5G-NC3-PadP5)") (class "Default")
      (node (ref "MN5") (pin "P5") (pinfunction "NC3_P5") (pintype "passive"))
    )
    (net (code "206") (name "unconnected-(MN5G-NC4-PadP6)") (class "Default")
      (node (ref "MN5") (pin "P6") (pinfunction "NC4_P6") (pintype "passive"))
    )
    (net (code "207") (name "unconnected-(MN5G-NC5-PadN3)") (class "Default")
      (node (ref "MN5") (pin "N3") (pinfunction "NC5_N3") (pintype "passive"))
    )
    (net (code "208") (name "unconnected-(MN5G-NC6-PadR4)") (class "Default")
      (node (ref "MN5") (pin "R4") (pinfunction "NC6_R4") (pintype "passive"))
    )
  )
)
